# p128necodrive.net
KiCad netlist of a schematic drawn in EAGLE
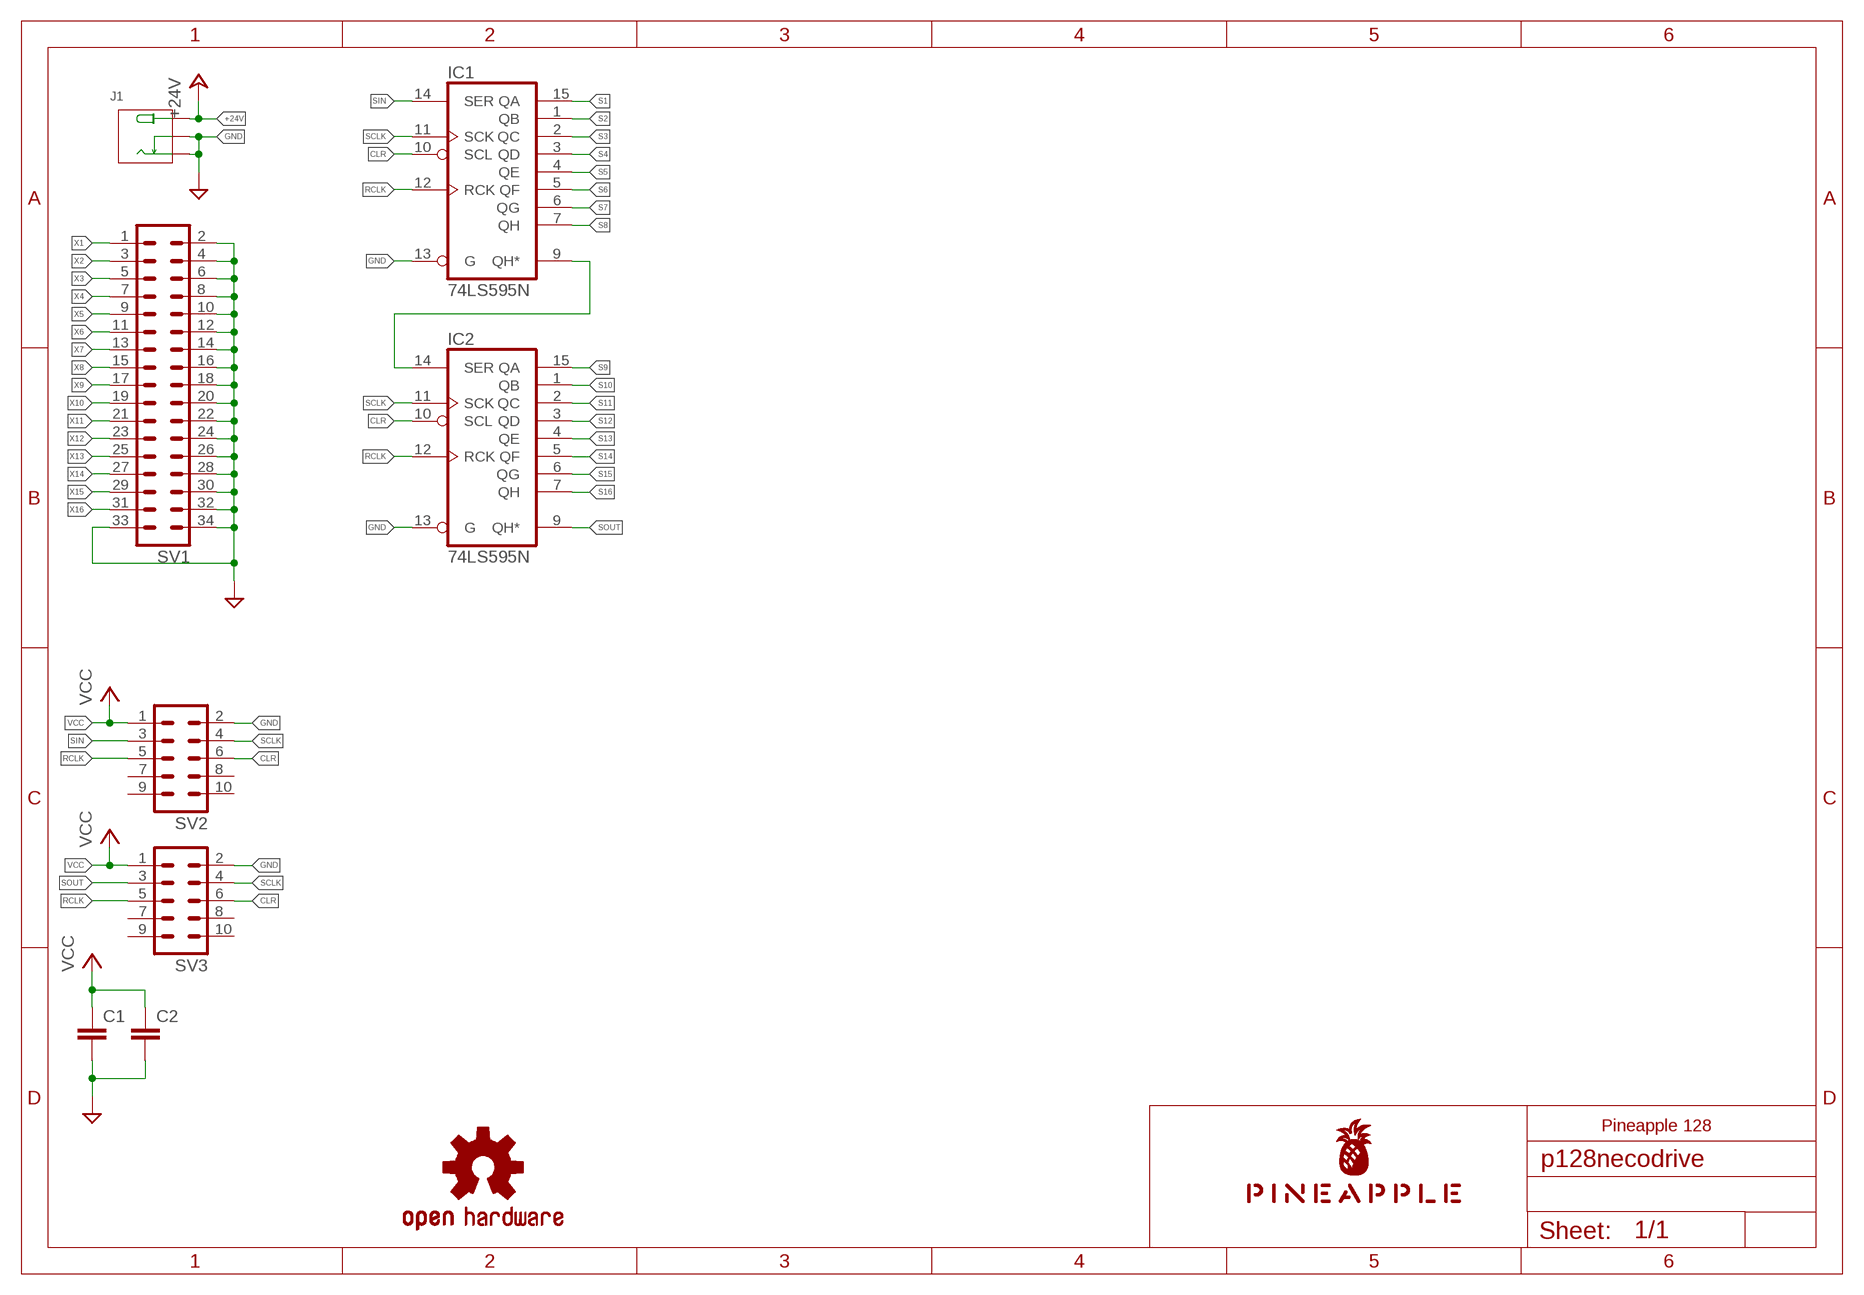
[diagram p0: schematic, sheet 1]

(export (version "E")
  (design (tool "Eeschema 10.0.6"))
  (components
    (comp (ref "C1")
      (value "C-EU025-024X044")
      (footprint "eagle-import:C025-024X044")
      (libsource (lib "eagle-import") (part "C-EU025-024X044"))
    )
    (comp (ref "C2")
      (value "C-EU025-024X044")
      (footprint "eagle-import:C025-024X044")
      (libsource (lib "eagle-import") (part "C-EU025-024X044"))
    )
    (comp (ref "IC1")
      (value "74LS595N")
      (footprint "eagle-import:DIL16")
      (libsource (lib "eagle-import") (part "74595NLS"))
    )
    (comp (ref "IC2")
      (value "74LS595N")
      (footprint "eagle-import:DIL16")
      (libsource (lib "eagle-import") (part "74595NLS"))
    )
    (comp (ref "J1")
      (value "JACK-DC-005'DC-005'")
      (footprint "eagle-import:3P-L14.2_W11.0_H9.0MM")
      (libsource (lib "eagle-import") (part "JACK-DC-005'DC-005'"))
    )
    (comp (ref "LOGO1")
      (value "OSHW-LOGOS-COPPER")
      (footprint "eagle-import:OSHW-LOGO-S_COPPER")
      (libsource (lib "eagle-import") (part "OSHW-LOGOS-COPPER"))
    )
    (comp (ref "SV1")
      (value "ML34L")
      (footprint "eagle-import:ML34L")
      (libsource (lib "eagle-import") (part "ML34L"))
    )
    (comp (ref "SV2")
      (value "ML10L")
      (footprint "eagle-import:ML10L")
      (libsource (lib "eagle-import") (part "ML10L"))
    )
    (comp (ref "SV3")
      (value "ML10L")
      (footprint "eagle-import:ML10L")
      (libsource (lib "eagle-import") (part "ML10L"))
    )
    (comp (ref "U$1")
      (value "PINEAPPLE450_SILK")
      (footprint "eagle-import:PINEAPPLE450_SILK")
      (libsource (lib "eagle-import") (part "PINEAPPLE450_SILK"))
    )
  )
  (nets
    (net (code "1") (name "+24V") (class "Default")
      (node (ref "J1") (pin "+") (pinfunction "+_+") (pintype "bidirectional"))
    )
    (net (code "2") (name "CLR") (class "Default")
      (node (ref "IC1") (pin "10") (pinfunction "SCL_10") (pintype "input"))
      (node (ref "IC2") (pin "10") (pinfunction "SCL_10") (pintype "input"))
      (node (ref "SV2") (pin "6") (pinfunction "6_6") (pintype "passive"))
      (node (ref "SV3") (pin "6") (pinfunction "6_6") (pintype "passive"))
    )
    (net (code "3") (name "GND") (class "Default")
      (node (ref "C1") (pin "2") (pinfunction "2_2") (pintype "passive"))
      (node (ref "C2") (pin "2") (pinfunction "2_2") (pintype "passive"))
      (node (ref "IC1") (pin "13") (pinfunction "G_13") (pintype "input"))
      (node (ref "IC2") (pin "13") (pinfunction "G_13") (pintype "input"))
      (node (ref "J1") (pin "-1") (pinfunction "-_-1") (pintype "bidirectional"))
      (node (ref "J1") (pin "-2") (pinfunction "CDN_-2") (pintype "bidirectional"))
      (node (ref "SV1") (pin "10") (pinfunction "10_10") (pintype "passive"))
      (node (ref "SV1") (pin "12") (pinfunction "12_12") (pintype "passive"))
      (node (ref "SV1") (pin "14") (pinfunction "14_14") (pintype "passive"))
      (node (ref "SV1") (pin "16") (pinfunction "16_16") (pintype "passive"))
      (node (ref "SV1") (pin "18") (pinfunction "18_18") (pintype "passive"))
      (node (ref "SV1") (pin "2") (pinfunction "2_2") (pintype "passive"))
      (node (ref "SV1") (pin "20") (pinfunction "20_20") (pintype "passive"))
      (node (ref "SV1") (pin "22") (pinfunction "22_22") (pintype "passive"))
      (node (ref "SV1") (pin "24") (pinfunction "24_24") (pintype "passive"))
      (node (ref "SV1") (pin "26") (pinfunction "26_26") (pintype "passive"))
      (node (ref "SV1") (pin "28") (pinfunction "28_28") (pintype "passive"))
      (node (ref "SV1") (pin "30") (pinfunction "30_30") (pintype "passive"))
      (node (ref "SV1") (pin "32") (pinfunction "32_32") (pintype "passive"))
      (node (ref "SV1") (pin "33") (pinfunction "33_33") (pintype "passive"))
      (node (ref "SV1") (pin "34") (pinfunction "34_34") (pintype "passive"))
      (node (ref "SV1") (pin "4") (pinfunction "4_4") (pintype "passive"))
      (node (ref "SV1") (pin "6") (pinfunction "6_6") (pintype "passive"))
      (node (ref "SV1") (pin "8") (pinfunction "8_8") (pintype "passive"))
      (node (ref "SV2") (pin "2") (pinfunction "2_2") (pintype "passive"))
      (node (ref "SV3") (pin "2") (pinfunction "2_2") (pintype "passive"))
    )
    (net (code "4") (name "Net-(IC1A-QH*)") (class "Default")
      (node (ref "IC1") (pin "9") (pinfunction "QH*_9") (pintype "tri_state"))
      (node (ref "IC2") (pin "14") (pinfunction "SER_14") (pintype "input"))
    )
    (net (code "5") (name "RCLK") (class "Default")
      (node (ref "IC1") (pin "12") (pinfunction "RCK_12") (pintype "input"))
      (node (ref "IC2") (pin "12") (pinfunction "RCK_12") (pintype "input"))
      (node (ref "SV2") (pin "5") (pinfunction "5_5") (pintype "passive"))
      (node (ref "SV3") (pin "5") (pinfunction "5_5") (pintype "passive"))
    )
    (net (code "6") (name "S1") (class "Default")
      (node (ref "IC1") (pin "15") (pinfunction "QA_15") (pintype "tri_state"))
    )
    (net (code "7") (name "S2") (class "Default")
      (node (ref "IC1") (pin "1") (pinfunction "QB_1") (pintype "tri_state"))
    )
    (net (code "8") (name "S3") (class "Default")
      (node (ref "IC1") (pin "2") (pinfunction "QC_2") (pintype "tri_state"))
    )
    (net (code "9") (name "S4") (class "Default")
      (node (ref "IC1") (pin "3") (pinfunction "QD_3") (pintype "tri_state"))
    )
    (net (code "10") (name "S5") (class "Default")
      (node (ref "IC1") (pin "4") (pinfunction "QE_4") (pintype "tri_state"))
    )
    (net (code "11") (name "S6") (class "Default")
      (node (ref "IC1") (pin "5") (pinfunction "QF_5") (pintype "tri_state"))
    )
    (net (code "12") (name "S7") (class "Default")
      (node (ref "IC1") (pin "6") (pinfunction "QG_6") (pintype "tri_state"))
    )
    (net (code "13") (name "S8") (class "Default")
      (node (ref "IC1") (pin "7") (pinfunction "QH_7") (pintype "tri_state"))
    )
    (net (code "14") (name "S9") (class "Default")
      (node (ref "IC2") (pin "15") (pinfunction "QA_15") (pintype "tri_state"))
    )
    (net (code "15") (name "S10") (class "Default")
      (node (ref "IC2") (pin "1") (pinfunction "QB_1") (pintype "tri_state"))
    )
    (net (code "16") (name "S11") (class "Default")
      (node (ref "IC2") (pin "2") (pinfunction "QC_2") (pintype "tri_state"))
    )
    (net (code "17") (name "S12") (class "Default")
      (node (ref "IC2") (pin "3") (pinfunction "QD_3") (pintype "tri_state"))
    )
    (net (code "18") (name "S13") (class "Default")
      (node (ref "IC2") (pin "4") (pinfunction "QE_4") (pintype "tri_state"))
    )
    (net (code "19") (name "S14") (class "Default")
      (node (ref "IC2") (pin "5") (pinfunction "QF_5") (pintype "tri_state"))
    )
    (net (code "20") (name "S15") (class "Default")
      (node (ref "IC2") (pin "6") (pinfunction "QG_6") (pintype "tri_state"))
    )
    (net (code "21") (name "S16") (class "Default")
      (node (ref "IC2") (pin "7") (pinfunction "QH_7") (pintype "tri_state"))
    )
    (net (code "22") (name "SCLK") (class "Default")
      (node (ref "IC1") (pin "11") (pinfunction "SCK_11") (pintype "input"))
      (node (ref "IC2") (pin "11") (pinfunction "SCK_11") (pintype "input"))
      (node (ref "SV2") (pin "4") (pinfunction "4_4") (pintype "passive"))
      (node (ref "SV3") (pin "4") (pinfunction "4_4") (pintype "passive"))
    )
    (net (code "23") (name "SIN") (class "Default")
      (node (ref "IC1") (pin "14") (pinfunction "SER_14") (pintype "input"))
      (node (ref "SV2") (pin "3") (pinfunction "3_3") (pintype "passive"))
    )
    (net (code "24") (name "SOUT") (class "Default")
      (node (ref "IC2") (pin "9") (pinfunction "QH*_9") (pintype "tri_state"))
      (node (ref "SV3") (pin "3") (pinfunction "3_3") (pintype "passive"))
    )
    (net (code "25") (name "VCC") (class "Default")
      (node (ref "C1") (pin "1") (pinfunction "1_1") (pintype "passive"))
      (node (ref "C2") (pin "1") (pinfunction "1_1") (pintype "passive"))
      (node (ref "SV2") (pin "1") (pinfunction "1_1") (pintype "passive"))
      (node (ref "SV3") (pin "1") (pinfunction "1_1") (pintype "passive"))
    )
    (net (code "26") (name "X1") (class "Default")
      (node (ref "SV1") (pin "1") (pinfunction "1_1") (pintype "passive"))
    )
    (net (code "27") (name "X2") (class "Default")
      (node (ref "SV1") (pin "3") (pinfunction "3_3") (pintype "passive"))
    )
    (net (code "28") (name "X3") (class "Default")
      (node (ref "SV1") (pin "5") (pinfunction "5_5") (pintype "passive"))
    )
    (net (code "29") (name "X4") (class "Default")
      (node (ref "SV1") (pin "7") (pinfunction "7_7") (pintype "passive"))
    )
    (net (code "30") (name "X5") (class "Default")
      (node (ref "SV1") (pin "9") (pinfunction "9_9") (pintype "passive"))
    )
    (net (code "31") (name "X6") (class "Default")
      (node (ref "SV1") (pin "11") (pinfunction "11_11") (pintype "passive"))
    )
    (net (code "32") (name "X7") (class "Default")
      (node (ref "SV1") (pin "13") (pinfunction "13_13") (pintype "passive"))
    )
    (net (code "33") (name "X8") (class "Default")
      (node (ref "SV1") (pin "15") (pinfunction "15_15") (pintype "passive"))
    )
    (net (code "34") (name "X9") (class "Default")
      (node (ref "SV1") (pin "17") (pinfunction "17_17") (pintype "passive"))
    )
    (net (code "35") (name "X10") (class "Default")
      (node (ref "SV1") (pin "19") (pinfunction "19_19") (pintype "passive"))
    )
    (net (code "36") (name "X11") (class "Default")
      (node (ref "SV1") (pin "21") (pinfunction "21_21") (pintype "passive"))
    )
    (net (code "37") (name "X12") (class "Default")
      (node (ref "SV1") (pin "23") (pinfunction "23_23") (pintype "passive"))
    )
    (net (code "38") (name "X13") (class "Default")
      (node (ref "SV1") (pin "25") (pinfunction "25_25") (pintype "passive"))
    )
    (net (code "39") (name "X14") (class "Default")
      (node (ref "SV1") (pin "27") (pinfunction "27_27") (pintype "passive"))
    )
    (net (code "40") (name "X15") (class "Default")
      (node (ref "SV1") (pin "29") (pinfunction "29_29") (pintype "passive"))
    )
    (net (code "41") (name "X16") (class "Default")
      (node (ref "SV1") (pin "31") (pinfunction "31_31") (pintype "passive"))
    )
    (net (code "42") (name "unconnected-(SV2-Pad7)") (class "Default")
      (node (ref "SV2") (pin "7") (pinfunction "7_7") (pintype "passive"))
    )
    (net (code "43") (name "unconnected-(SV2-Pad8)") (class "Default")
      (node (ref "SV2") (pin "8") (pinfunction "8_8") (pintype "passive"))
    )
    (net (code "44") (name "unconnected-(SV2-Pad9)") (class "Default")
      (node (ref "SV2") (pin "9") (pinfunction "9_9") (pintype "passive"))
    )
    (net (code "45") (name "unconnected-(SV2-Pad10)") (class "Default")
      (node (ref "SV2") (pin "10") (pinfunction "10_10") (pintype "passive"))
    )
    (net (code "46") (name "unconnected-(SV3-Pad7)") (class "Default")
      (node (ref "SV3") (pin "7") (pinfunction "7_7") (pintype "passive"))
    )
    (net (code "47") (name "unconnected-(SV3-Pad8)") (class "Default")
      (node (ref "SV3") (pin "8") (pinfunction "8_8") (pintype "passive"))
    )
    (net (code "48") (name "unconnected-(SV3-Pad9)") (class "Default")
      (node (ref "SV3") (pin "9") (pinfunction "9_9") (pintype "passive"))
    )
    (net (code "49") (name "unconnected-(SV3-Pad10)") (class "Default")
      (node (ref "SV3") (pin "10") (pinfunction "10_10") (pintype "passive"))
    )
  )
)
